# SCH_NFC-Business-Card_2024-03-17.net
KiCad netlist of a schematic drawn in EasyEDA
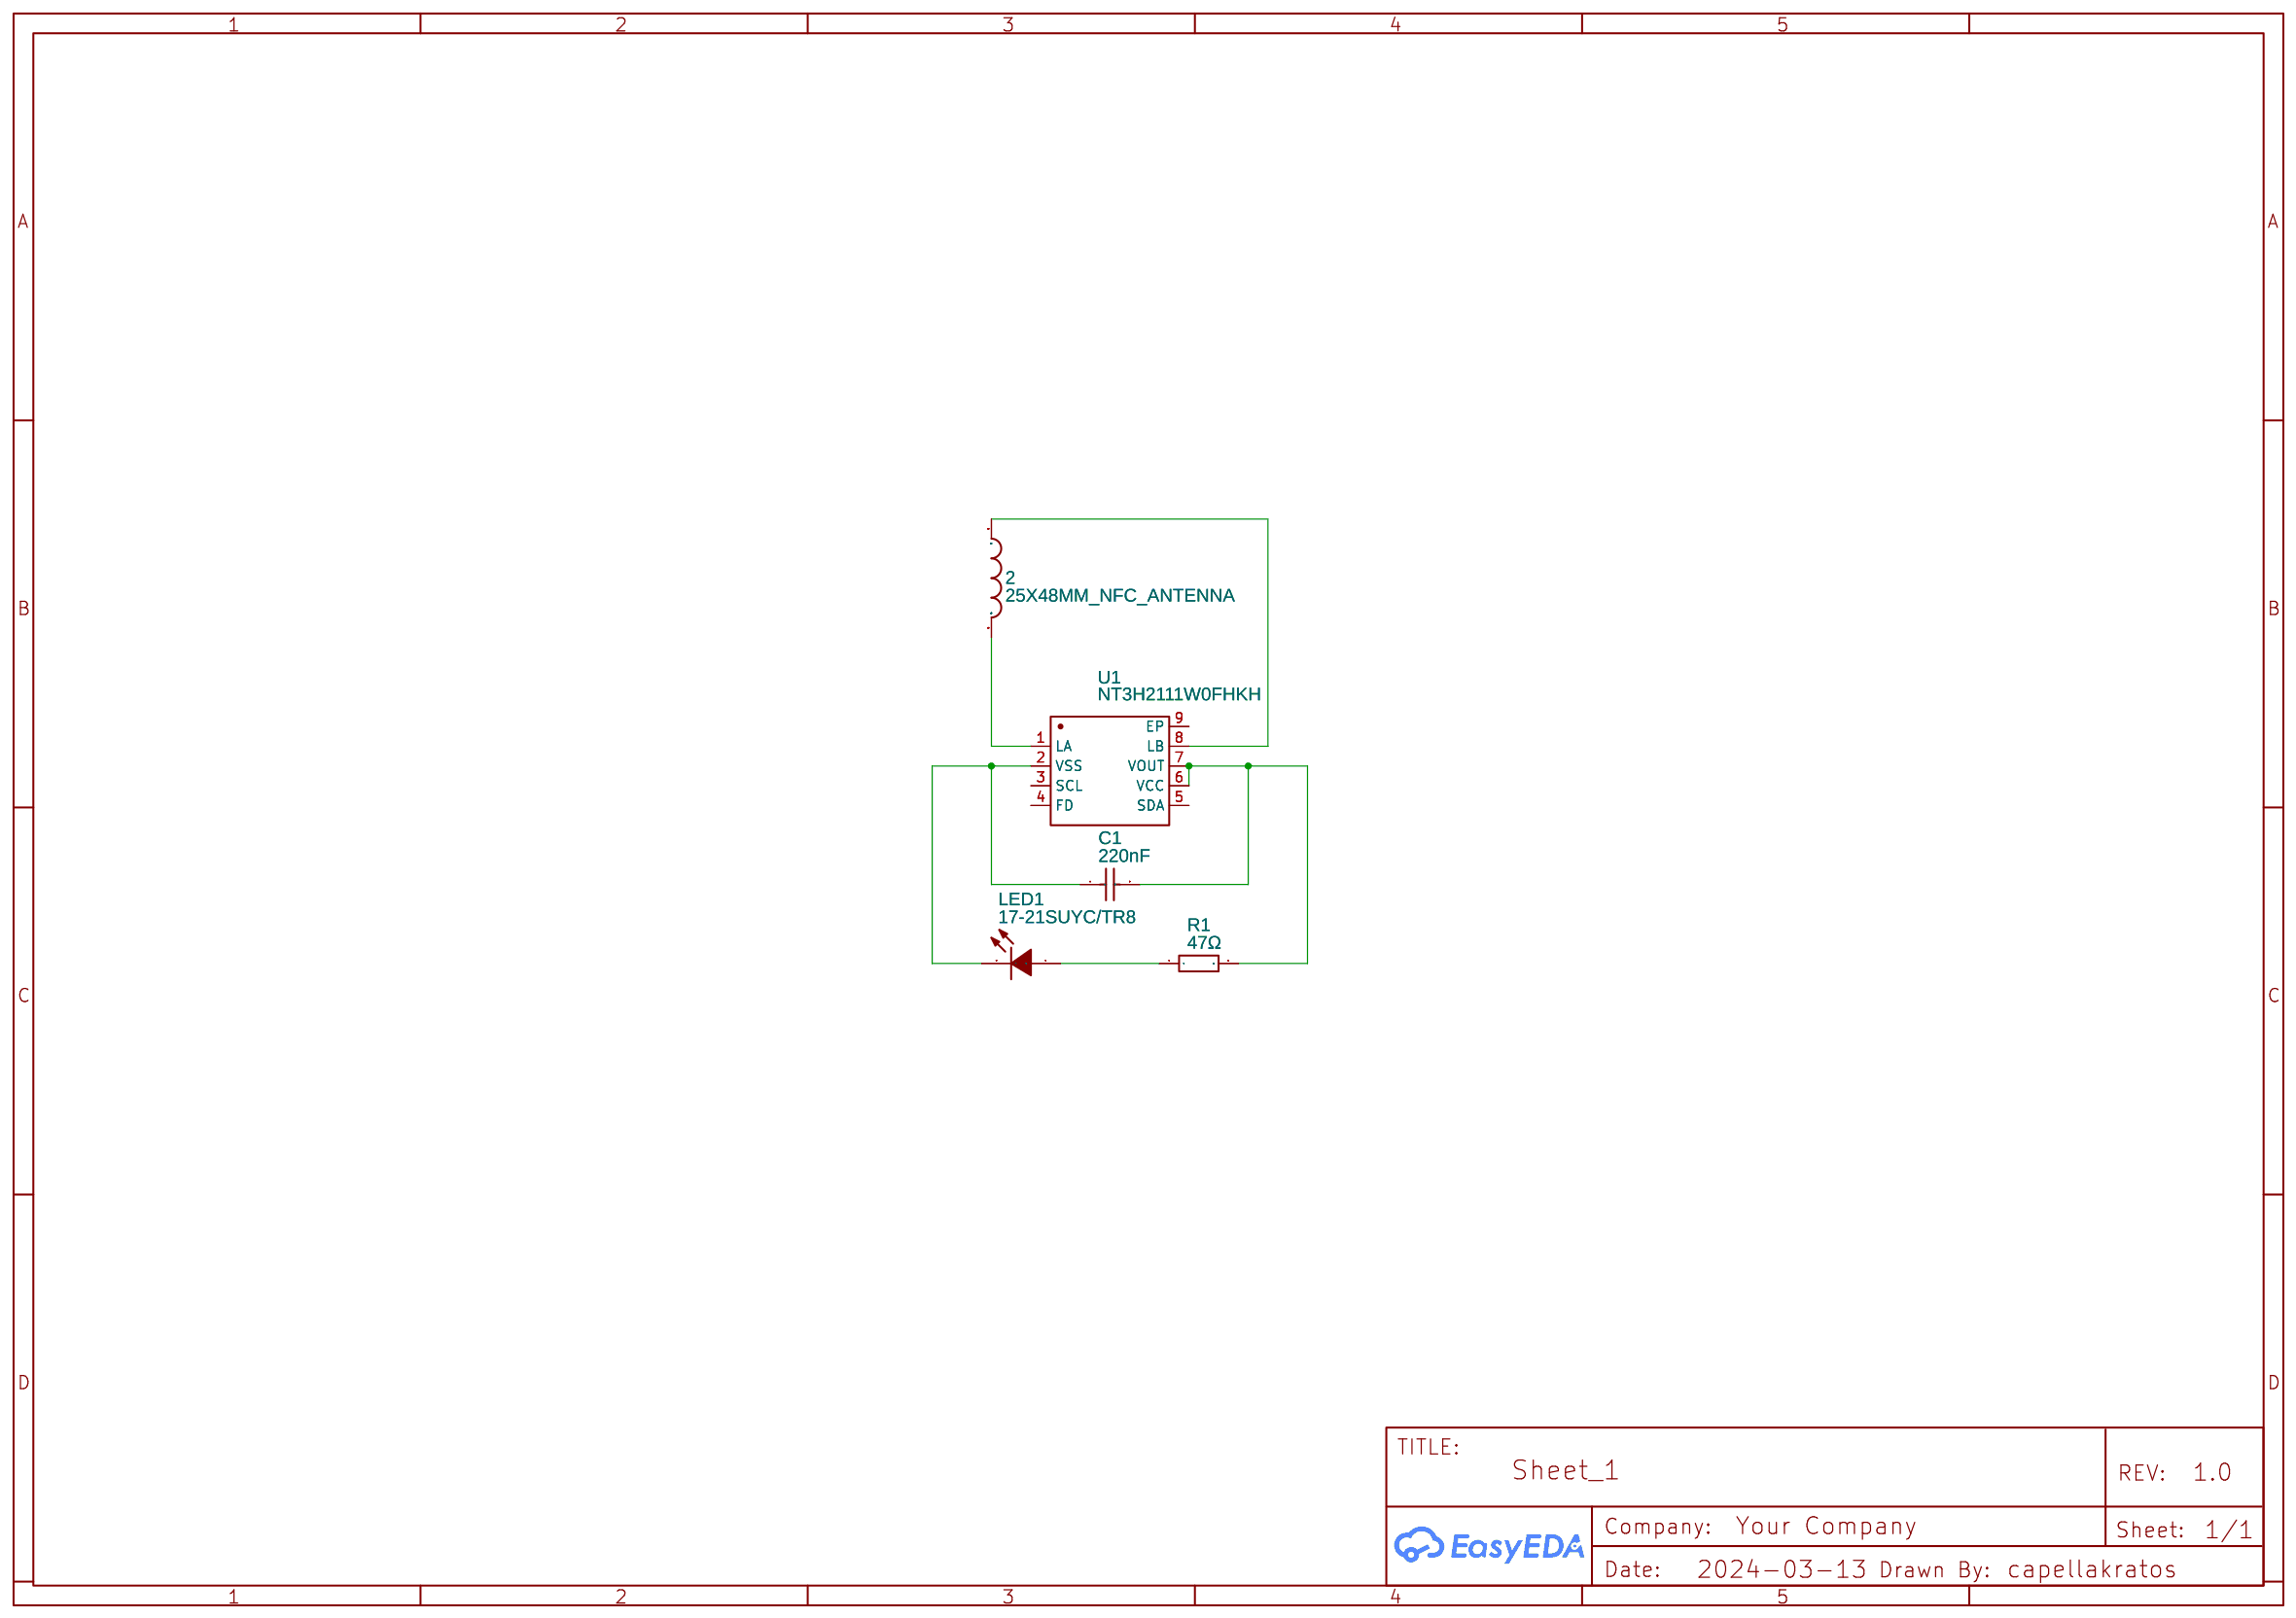
[diagram p0: schematic sheet]

(export (version "E")
  (design (tool "Eeschema 10.0.6"))
  (components
    (comp (ref "2") (value "25X48MM_NFC_ANTENNA") (libsource (lib "") (part "25X48MM_NFC_ANTENNA")))
    (comp (ref "C1")
      (value "220nF")
      (fields
        (field (name "Manufacturer Part") "CL10B224KA8NNNC")
        (field (name "Manufacturer") "SAMSUNG(三星)")
      )
      (libsource (lib "") (part "CL10B224KA8NNNC"))
    )
    (comp (ref "LED1")
      (value "17-21SUYC/TR8")
      (fields (field (name "Manufacturer Part") "KT-0805黄灯") (field (name "Manufacturer") "KENTO"))
      (libsource (lib "") (part "17-21SUYC/TR8"))
    )
    (comp (ref "R1")
      (value "47Ω")
      (fields
        (field (name "Manufacturer Part") "0603WAF470JT5E")
        (field (name "Manufacturer") "UNI-ROYAL(厚声)")
      )
      (libsource (lib "") (part "0603WAF470JT5E"))
    )
    (comp (ref "U1")
      (value "NT3H2111W0FHKH")
      (fields (field (name "Manufacturer") "NXP(恩智浦)"))
      (libsource (lib "") (part "NT3H2111W0FHKH"))
    )
  )
  (nets
    (net (code "1") (name "Net-(LED1-+)") (class "Default")
      (node (ref "LED1") (pin "1") (pinfunction "+_1") (pintype "unspecified"))
      (node (ref "R1") (pin "1") (pinfunction "1_1") (pintype "input"))
    )
    (net (code "2") (name "Net-(LED1--)") (class "Default")
      (node (ref "C1") (pin "1") (pinfunction "1_1") (pintype "input"))
      (node (ref "LED1") (pin "2") (pinfunction "-_2") (pintype "unspecified"))
      (node (ref "U1") (pin "2") (pinfunction "VSS_2") (pintype "unspecified"))
    )
    (net (code "3") (name "Net-(U1-LA)") (class "Default")
      (node (ref "2") (pin "P$2") (pinfunction "P$2_P$2") (pintype "bidirectional"))
      (node (ref "U1") (pin "1") (pinfunction "LA_1") (pintype "unspecified"))
    )
    (net (code "4") (name "Net-(U1-LB)") (class "Default")
      (node (ref "2") (pin "P$1") (pinfunction "P$1_P$1") (pintype "bidirectional"))
      (node (ref "U1") (pin "8") (pinfunction "LB_8") (pintype "unspecified"))
    )
    (net (code "5") (name "Net-(U1-VCC)") (class "Default")
      (node (ref "C1") (pin "2") (pinfunction "2_2") (pintype "input"))
      (node (ref "R1") (pin "2") (pinfunction "2_2") (pintype "input"))
      (node (ref "U1") (pin "6") (pinfunction "VCC_6") (pintype "unspecified"))
      (node (ref "U1") (pin "7") (pinfunction "VOUT_7") (pintype "unspecified"))
    )
    (net (code "6") (name "unconnected-(U1-EP-Pad9)") (class "Default")
      (node (ref "U1") (pin "9") (pinfunction "EP_9") (pintype "unspecified"))
    )
    (net (code "7") (name "unconnected-(U1-FD-Pad4)") (class "Default")
      (node (ref "U1") (pin "4") (pinfunction "FD_4") (pintype "unspecified"))
    )
    (net (code "8") (name "unconnected-(U1-SCL-Pad3)") (class "Default")
      (node (ref "U1") (pin "3") (pinfunction "SCL_3") (pintype "unspecified"))
    )
    (net (code "9") (name "unconnected-(U1-SDA-Pad5)") (class "Default")
      (node (ref "U1") (pin "5") (pinfunction "SDA_5") (pintype "unspecified"))
    )
  )
)
